# Continuity_Tester.net
KiCad netlist of a schematic drawn in EAGLE
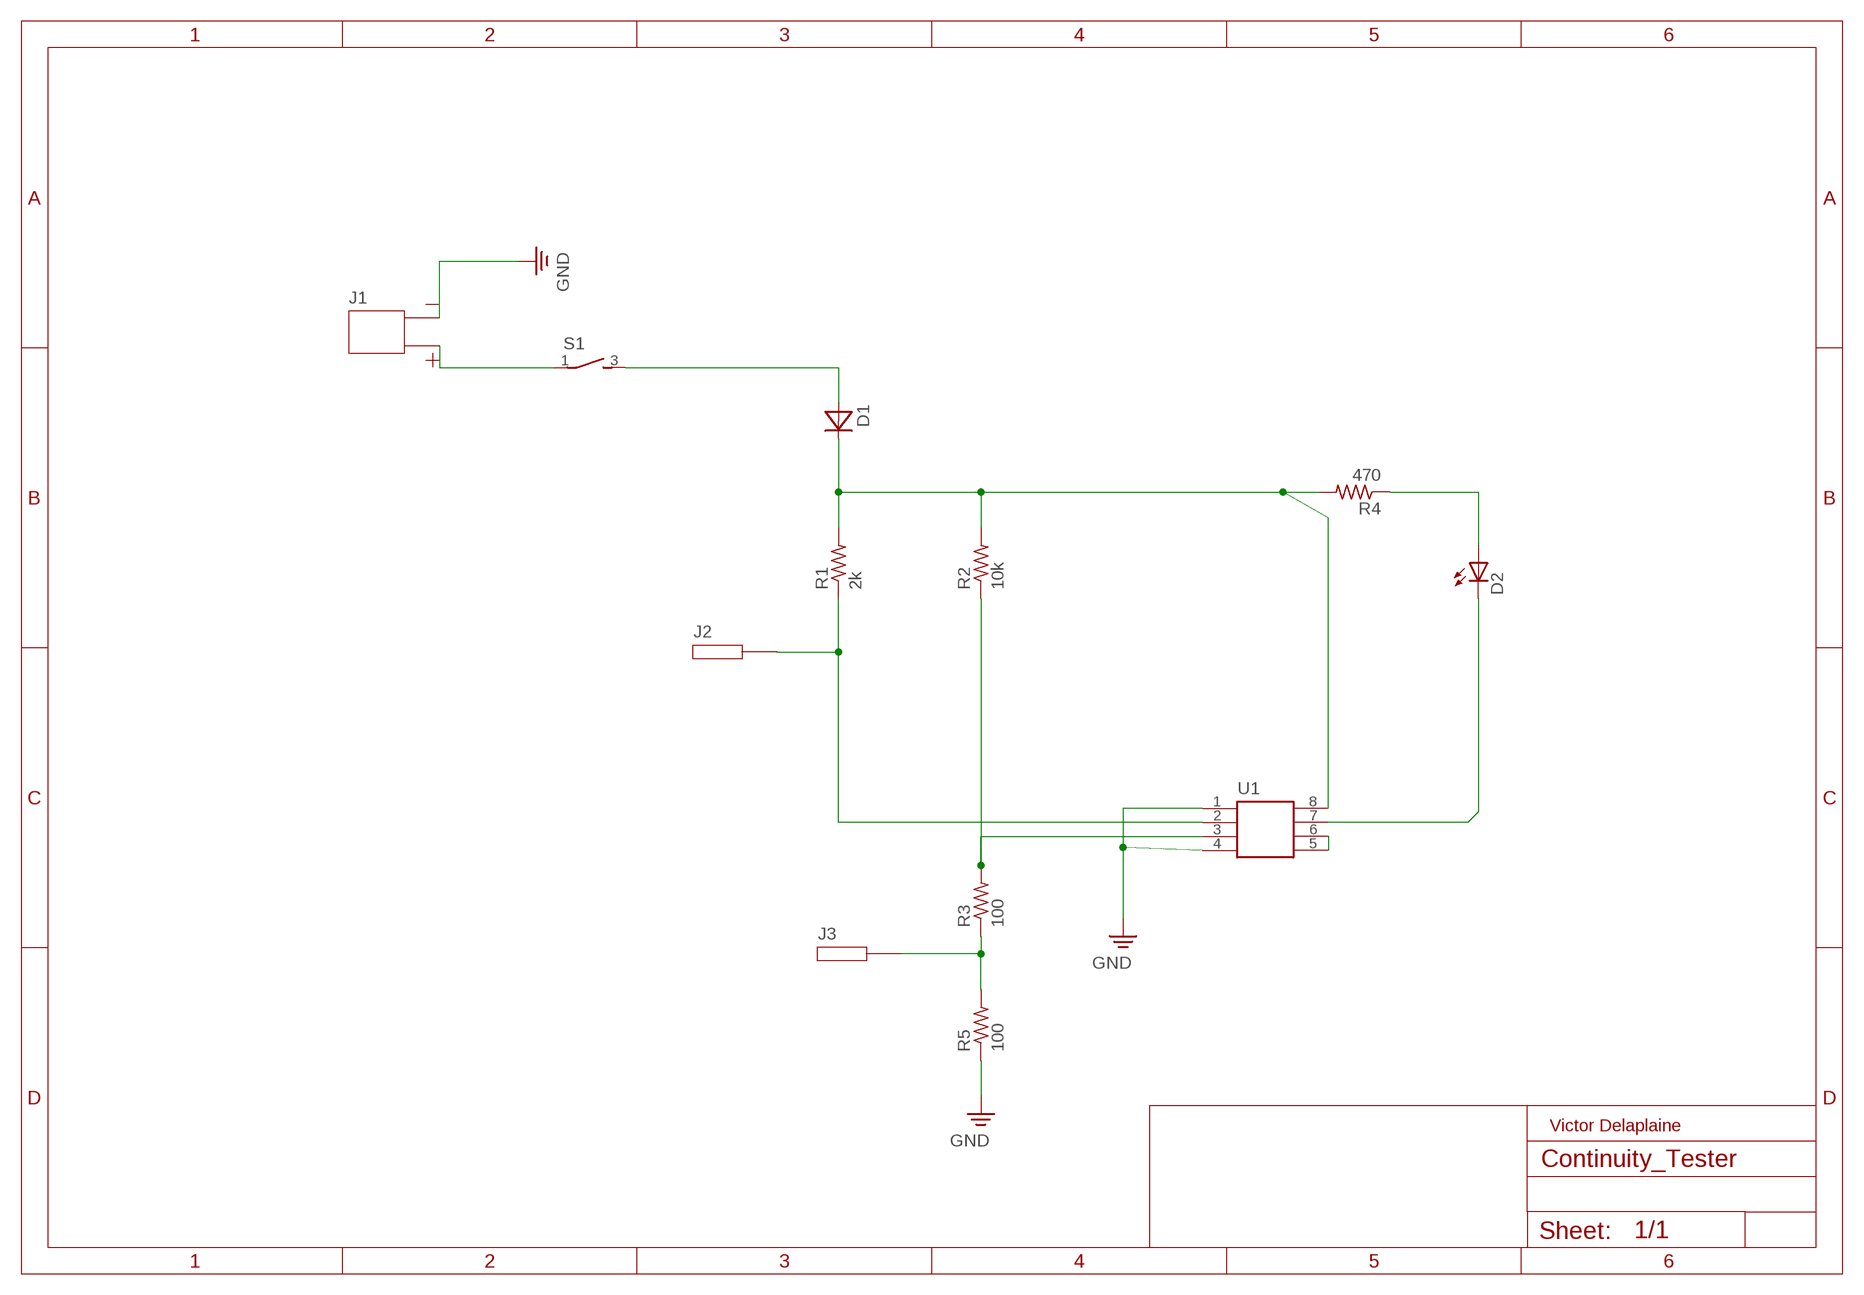
[diagram p0: schematic, sheet 1]

(export (version "E")
  (design (tool "Eeschema 10.0.6"))
  (components
    (comp (ref "D1")
      (value "DIODE")
      (footprint "eagle-import:DIODE-FOOT")
      (libsource (lib "eagle-import") (part "DIODE"))
    )
    (comp (ref "D2")
      (value "LED")
      (footprint "eagle-import:LED-FOOT")
      (libsource (lib "eagle-import") (part "LED"))
    )
    (comp (ref "J1")
      (value "POWER")
      (footprint "eagle-import:POWER-FOOT")
      (libsource (lib "eagle-import") (part "POWER"))
    )
    (comp (ref "J2")
      (value "ALLIGATORCLIP")
      (footprint "eagle-import:ALLIGATORCLIP-FOOT")
      (libsource (lib "eagle-import") (part "ALLIGATORCLIP"))
    )
    (comp (ref "J3")
      (value "ALLIGATORCLIP")
      (footprint "eagle-import:ALLIGATORCLIP-FOOT")
      (libsource (lib "eagle-import") (part "ALLIGATORCLIP"))
    )
    (comp (ref "R1")
      (value "2k")
      (footprint "eagle-import:RES-FOOT")
      (libsource (lib "eagle-import") (part "RES"))
    )
    (comp (ref "R2")
      (value "10k")
      (footprint "eagle-import:RES-FOOT")
      (libsource (lib "eagle-import") (part "RES"))
    )
    (comp (ref "R3")
      (value "100")
      (footprint "eagle-import:RES-FOOT")
      (libsource (lib "eagle-import") (part "RES"))
    )
    (comp (ref "R4")
      (value "470")
      (footprint "eagle-import:RES-FOOT")
      (libsource (lib "eagle-import") (part "RES"))
    )
    (comp (ref "R5")
      (value "100")
      (footprint "eagle-import:RES-FOOT")
      (libsource (lib "eagle-import") (part "RES"))
    )
    (comp (ref "S1")
      (value "SWITCH")
      (footprint "eagle-import:SWITCH-FOOT")
      (libsource (lib "eagle-import") (part "SWITCH"))
    )
    (comp (ref "U1")
      (value "LM311M")
      (footprint "eagle-import:LM311M-FOOT")
      (libsource (lib "eagle-import") (part "LM311M"))
    )
  )
  (nets
    (net (code "1") (name "GND") (class "Default")
      (node (ref "J1") (pin "1") (pinfunction "1_1") (pintype "bidirectional"))
      (node (ref "R5") (pin "1") (pinfunction "1_1") (pintype "passive"))
      (node (ref "U1") (pin "1") (pinfunction "1_1") (pintype "bidirectional"))
      (node (ref "U1") (pin "4") (pinfunction "4_4") (pintype "bidirectional"))
    )
    (net (code "2") (name "Net-(D1-PadA)") (class "Default")
      (node (ref "D1") (pin "A") (pinfunction "A_A") (pintype "passive"))
      (node (ref "S1") (pin "3") (pinfunction "3_3") (pintype "passive"))
    )
    (net (code "3") (name "Net-(D1-PadC)") (class "Default")
      (node (ref "D1") (pin "C") (pinfunction "C_C") (pintype "passive"))
      (node (ref "R1") (pin "2") (pinfunction "2_2") (pintype "passive"))
      (node (ref "R2") (pin "2") (pinfunction "2_2") (pintype "passive"))
      (node (ref "R4") (pin "2") (pinfunction "2_2") (pintype "passive"))
      (node (ref "U1") (pin "8") (pinfunction "8_8") (pintype "bidirectional"))
    )
    (net (code "4") (name "Net-(D2-PadA)") (class "Default")
      (node (ref "D2") (pin "A") (pinfunction "A_A") (pintype "passive"))
      (node (ref "R4") (pin "1") (pinfunction "1_1") (pintype "passive"))
    )
    (net (code "5") (name "Net-(D2-PadC)") (class "Default")
      (node (ref "D2") (pin "C") (pinfunction "C_C") (pintype "passive"))
      (node (ref "U1") (pin "7") (pinfunction "7_7") (pintype "bidirectional"))
    )
    (net (code "6") (name "Net-(J1-Pad2)") (class "Default")
      (node (ref "J1") (pin "2") (pinfunction "2_2") (pintype "bidirectional"))
      (node (ref "S1") (pin "1") (pinfunction "1_1") (pintype "passive"))
    )
    (net (code "7") (name "Net-(J2-Pad1)") (class "Default")
      (node (ref "J2") (pin "1") (pinfunction "1_1") (pintype "bidirectional"))
      (node (ref "R1") (pin "1") (pinfunction "1_1") (pintype "passive"))
      (node (ref "U1") (pin "2") (pinfunction "2_2") (pintype "bidirectional"))
    )
    (net (code "8") (name "Net-(J3-Pad1)") (class "Default")
      (node (ref "J3") (pin "1") (pinfunction "1_1") (pintype "bidirectional"))
      (node (ref "R3") (pin "1") (pinfunction "1_1") (pintype "passive"))
      (node (ref "R5") (pin "2") (pinfunction "2_2") (pintype "passive"))
    )
    (net (code "9") (name "Net-(R2-Pad1)") (class "Default")
      (node (ref "R2") (pin "1") (pinfunction "1_1") (pintype "passive"))
      (node (ref "R3") (pin "2") (pinfunction "2_2") (pintype "passive"))
      (node (ref "U1") (pin "3") (pinfunction "3_3") (pintype "bidirectional"))
    )
    (net (code "10") (name "Net-(U1-Pad5)") (class "Default")
      (node (ref "U1") (pin "5") (pinfunction "5_5") (pintype "bidirectional"))
      (node (ref "U1") (pin "6") (pinfunction "6_6") (pintype "bidirectional"))
    )
  )
)
